# bmsMaster_conn.net
KiCad netlist of a schematic drawn in Altium Designer
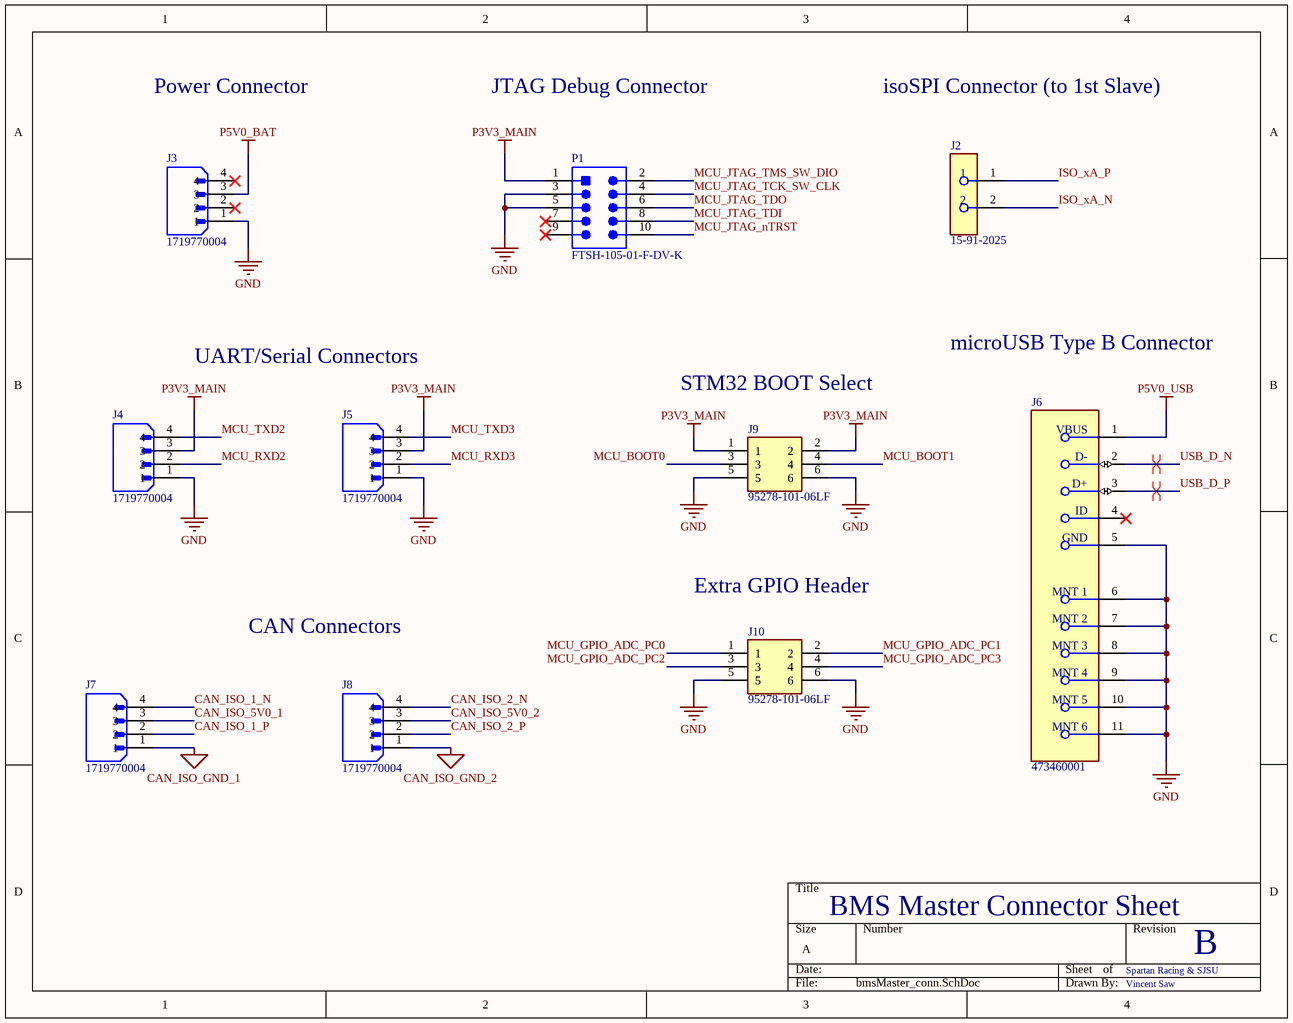
[diagram p0: bmsMaster_conn.SchDoc]

(export (version "E")
  (design (tool "Eeschema 10.0.6"))
  (components
    (comp (ref "J2")
      (value "15-91-2025")
      (footprint "FP-15-91-2025-MFG")
      (description "CONN HEADER SMD R/A 2POS 2.54MM")
      (libsource (lib "Altium Content Vault") (part "3ddab50f66188bb7952c54a1b76274c"))
    )
    (comp (ref "J3")
      (value "1719770004")
      (footprint "171977-0004:MOLEX_1719770004")
      (fields (field (name "MF") "{'manufacturer': u'Molex'}"))
      (libsource (lib "*") (part "1719770004"))
    )
    (comp (ref "J4")
      (value "1719770004")
      (footprint "171977-0004:MOLEX_1719770004")
      (fields (field (name "MF") "{'manufacturer': u'Molex'}"))
      (libsource (lib "*") (part "1719770004"))
    )
    (comp (ref "J5")
      (value "1719770004")
      (footprint "171977-0004:MOLEX_1719770004")
      (fields (field (name "MF") "{'manufacturer': u'Molex'}"))
      (libsource (lib "*") (part "1719770004"))
    )
    (comp (ref "J6")
      (value "473460001")
      (footprint "FP-473460001-MFG")
      (description "CONN RCPT USB2.0 MICRO B SMD R/A")
      (fields
        (field (name "OCTOPART") "https://octopart.com/47346-0001-molex-7164928")
        (field (name "MANUFACTURER") "Molex")
      )
      (libsource (lib "Altium Content Vault") (part "53ae1f1d9b557310b43ca686e5bb76a"))
    )
    (comp (ref "J7")
      (value "1719770004")
      (footprint "171977-0004:MOLEX_1719770004")
      (fields (field (name "MF") "{'manufacturer': u'Molex'}"))
      (libsource (lib "*") (part "1719770004"))
    )
    (comp (ref "J8")
      (value "1719770004")
      (footprint "171977-0004:MOLEX_1719770004")
      (fields (field (name "MF") "{'manufacturer': u'Molex'}"))
      (libsource (lib "*") (part "1719770004"))
    )
    (comp (ref "J9")
      (value "95278-101-06LF")
      (footprint "SamacSys:9527810106LF")
      (description "Connector")
      (fields (field (name "MOUSER PART NUMBER") "649-95278-101-06LF"))
      (libsource (lib "*") (part "95278-101-06LF"))
    )
    (comp (ref "J10")
      (value "95278-101-06LF")
      (footprint "SamacSys:9527810106LF")
      (description "Connector")
      (fields (field (name "MOUSER PART NUMBER") "649-95278-101-06LF"))
      (libsource (lib "*") (part "95278-101-06LF"))
    )
    (comp (ref "P1")
      (value "FTSH-105-01-F-DV-K")
      (footprint "SMTC-FTSH-105-01-L-DV-K_V")
      (description "Male Header, Pitch 1.27 mm, 2 x 5 Position, Height 6.12 mm, RoHS, Tube")
      (fields (field (name "MANUFACTURER") "Samtec"))
      (libsource (lib "Altium Content Vault") (part "CN-2P-M-R10"))
    )
  )
  (nets
    (net (code "1") (name "/CAN_ISO_1_N") (class "Default")
      (node (ref "J7") (pin "4") (pinfunction "4_4") (pintype "passive"))
    )
    (net (code "2") (name "/CAN_ISO_1_P") (class "Default")
      (node (ref "J7") (pin "2") (pinfunction "2_2") (pintype "passive"))
    )
    (net (code "3") (name "/CAN_ISO_2_N") (class "Default")
      (node (ref "J8") (pin "4") (pinfunction "4_4") (pintype "passive"))
    )
    (net (code "4") (name "/CAN_ISO_2_P") (class "Default")
      (node (ref "J8") (pin "2") (pinfunction "2_2") (pintype "passive"))
    )
    (net (code "5") (name "/CAN_ISO_5V0_1") (class "Default")
      (node (ref "J7") (pin "3") (pinfunction "3_3") (pintype "passive"))
    )
    (net (code "6") (name "/CAN_ISO_5V0_2") (class "Default")
      (node (ref "J8") (pin "3") (pinfunction "3_3") (pintype "passive"))
    )
    (net (code "7") (name "/ISO_xA_N") (class "Default")
      (node (ref "J2") (pin "2") (pinfunction "2_2") (pintype "passive"))
    )
    (net (code "8") (name "/ISO_xA_P") (class "Default")
      (node (ref "J2") (pin "1") (pinfunction "1_1") (pintype "passive"))
    )
    (net (code "9") (name "/MCU_BOOT0") (class "Default")
      (node (ref "J9") (pin "3") (pinfunction "3_3") (pintype "passive"))
    )
    (net (code "10") (name "/MCU_BOOT1") (class "Default")
      (node (ref "J9") (pin "4") (pinfunction "4_4") (pintype "passive"))
    )
    (net (code "11") (name "/MCU_GPIO_ADC_PC0") (class "Default")
      (node (ref "J10") (pin "1") (pinfunction "1_1") (pintype "passive"))
    )
    (net (code "12") (name "/MCU_GPIO_ADC_PC1") (class "Default")
      (node (ref "J10") (pin "2") (pinfunction "2_2") (pintype "passive"))
    )
    (net (code "13") (name "/MCU_GPIO_ADC_PC2") (class "Default")
      (node (ref "J10") (pin "3") (pinfunction "3_3") (pintype "passive"))
    )
    (net (code "14") (name "/MCU_GPIO_ADC_PC3") (class "Default")
      (node (ref "J10") (pin "4") (pinfunction "4_4") (pintype "passive"))
    )
    (net (code "15") (name "/MCU_JTAG_TCK_SW_CLK") (class "Default")
      (node (ref "P1") (pin "4") (pinfunction "4_4") (pintype "passive"))
    )
    (net (code "16") (name "/MCU_JTAG_TDI") (class "Default")
      (node (ref "P1") (pin "8") (pinfunction "8_8") (pintype "passive"))
    )
    (net (code "17") (name "/MCU_JTAG_TDO") (class "Default")
      (node (ref "P1") (pin "6") (pinfunction "6_6") (pintype "passive"))
    )
    (net (code "18") (name "/MCU_JTAG_TMS_SW_DIO") (class "Default")
      (node (ref "P1") (pin "2") (pinfunction "2_2") (pintype "passive"))
    )
    (net (code "19") (name "/MCU_JTAG_nTRST") (class "Default")
      (node (ref "P1") (pin "10") (pinfunction "10_10") (pintype "passive"))
    )
    (net (code "20") (name "/MCU_RXD2") (class "Default")
      (node (ref "J4") (pin "2") (pinfunction "2_2") (pintype "passive"))
    )
    (net (code "21") (name "/MCU_RXD3") (class "Default")
      (node (ref "J5") (pin "2") (pinfunction "2_2") (pintype "passive"))
    )
    (net (code "22") (name "/MCU_TXD2") (class "Default")
      (node (ref "J4") (pin "4") (pinfunction "4_4") (pintype "passive"))
    )
    (net (code "23") (name "/MCU_TXD3") (class "Default")
      (node (ref "J5") (pin "4") (pinfunction "4_4") (pintype "passive"))
    )
    (net (code "24") (name "/USB_D_N") (class "Default")
      (node (ref "J6") (pin "2") (pinfunction "D-_2") (pintype "bidirectional"))
    )
    (net (code "25") (name "/USB_D_P") (class "Default")
      (node (ref "J6") (pin "3") (pinfunction "D+_3") (pintype "bidirectional"))
    )
    (net (code "26") (name "CAN_ISO_GND_1") (class "Default")
      (node (ref "J7") (pin "1") (pinfunction "1_1") (pintype "passive"))
    )
    (net (code "27") (name "CAN_ISO_GND_2") (class "Default")
      (node (ref "J8") (pin "1") (pinfunction "1_1") (pintype "passive"))
    )
    (net (code "28") (name "GND") (class "Default")
      (node (ref "J10") (pin "5") (pinfunction "5_5") (pintype "passive"))
      (node (ref "J10") (pin "6") (pinfunction "6_6") (pintype "passive"))
      (node (ref "J3") (pin "1") (pinfunction "1_1") (pintype "passive"))
      (node (ref "J4") (pin "1") (pinfunction "1_1") (pintype "passive"))
      (node (ref "J5") (pin "1") (pinfunction "1_1") (pintype "passive"))
      (node (ref "J6") (pin "10") (pinfunction "MNT_5_10") (pintype "passive"))
      (node (ref "J6") (pin "11") (pinfunction "MNT_6_11") (pintype "passive"))
      (node (ref "J6") (pin "5") (pinfunction "GND_5") (pintype "power_in"))
      (node (ref "J6") (pin "6") (pinfunction "MNT_1_6") (pintype "passive"))
      (node (ref "J6") (pin "7") (pinfunction "MNT_2_7") (pintype "passive"))
      (node (ref "J6") (pin "8") (pinfunction "MNT_3_8") (pintype "passive"))
      (node (ref "J6") (pin "9") (pinfunction "MNT_4_9") (pintype "passive"))
      (node (ref "J9") (pin "5") (pinfunction "5_5") (pintype "passive"))
      (node (ref "J9") (pin "6") (pinfunction "6_6") (pintype "passive"))
      (node (ref "P1") (pin "3") (pinfunction "3_3") (pintype "passive"))
      (node (ref "P1") (pin "5") (pinfunction "5_5") (pintype "passive"))
    )
    (net (code "29") (name "P3V3_MAIN") (class "Default")
      (node (ref "J4") (pin "3") (pinfunction "3_3") (pintype "passive"))
      (node (ref "J5") (pin "3") (pinfunction "3_3") (pintype "passive"))
      (node (ref "J9") (pin "1") (pinfunction "1_1") (pintype "passive"))
      (node (ref "J9") (pin "2") (pinfunction "2_2") (pintype "passive"))
      (node (ref "P1") (pin "1") (pinfunction "1_1") (pintype "passive"))
    )
    (net (code "30") (name "P5V0_BAT") (class "Default")
      (node (ref "J3") (pin "3") (pinfunction "3_3") (pintype "passive"))
    )
    (net (code "31") (name "P5V0_USB") (class "Default")
      (node (ref "J6") (pin "1") (pinfunction "VBUS_1") (pintype "power_in"))
    )
    (net (code "32") (name "unconnected-(J3-Pad2)") (class "Default")
      (node (ref "J3") (pin "2") (pinfunction "2_2") (pintype "passive+no_connect"))
    )
    (net (code "33") (name "unconnected-(J3-Pad4)") (class "Default")
      (node (ref "J3") (pin "4") (pinfunction "4_4") (pintype "passive+no_connect"))
    )
    (net (code "34") (name "unconnected-(J6-ID-Pad4)") (class "Default")
      (node (ref "J6") (pin "4") (pinfunction "ID_4") (pintype "passive+no_connect"))
    )
    (net (code "35") (name "unconnected-(P1-Pad7)") (class "Default")
      (node (ref "P1") (pin "7") (pinfunction "7_7") (pintype "passive+no_connect"))
    )
    (net (code "36") (name "unconnected-(P1-Pad9)") (class "Default")
      (node (ref "P1") (pin "9") (pinfunction "9_9") (pintype "passive+no_connect"))
    )
  )
)
